# MS5803-02BA.net
KiCad netlist of a schematic drawn in EAGLE
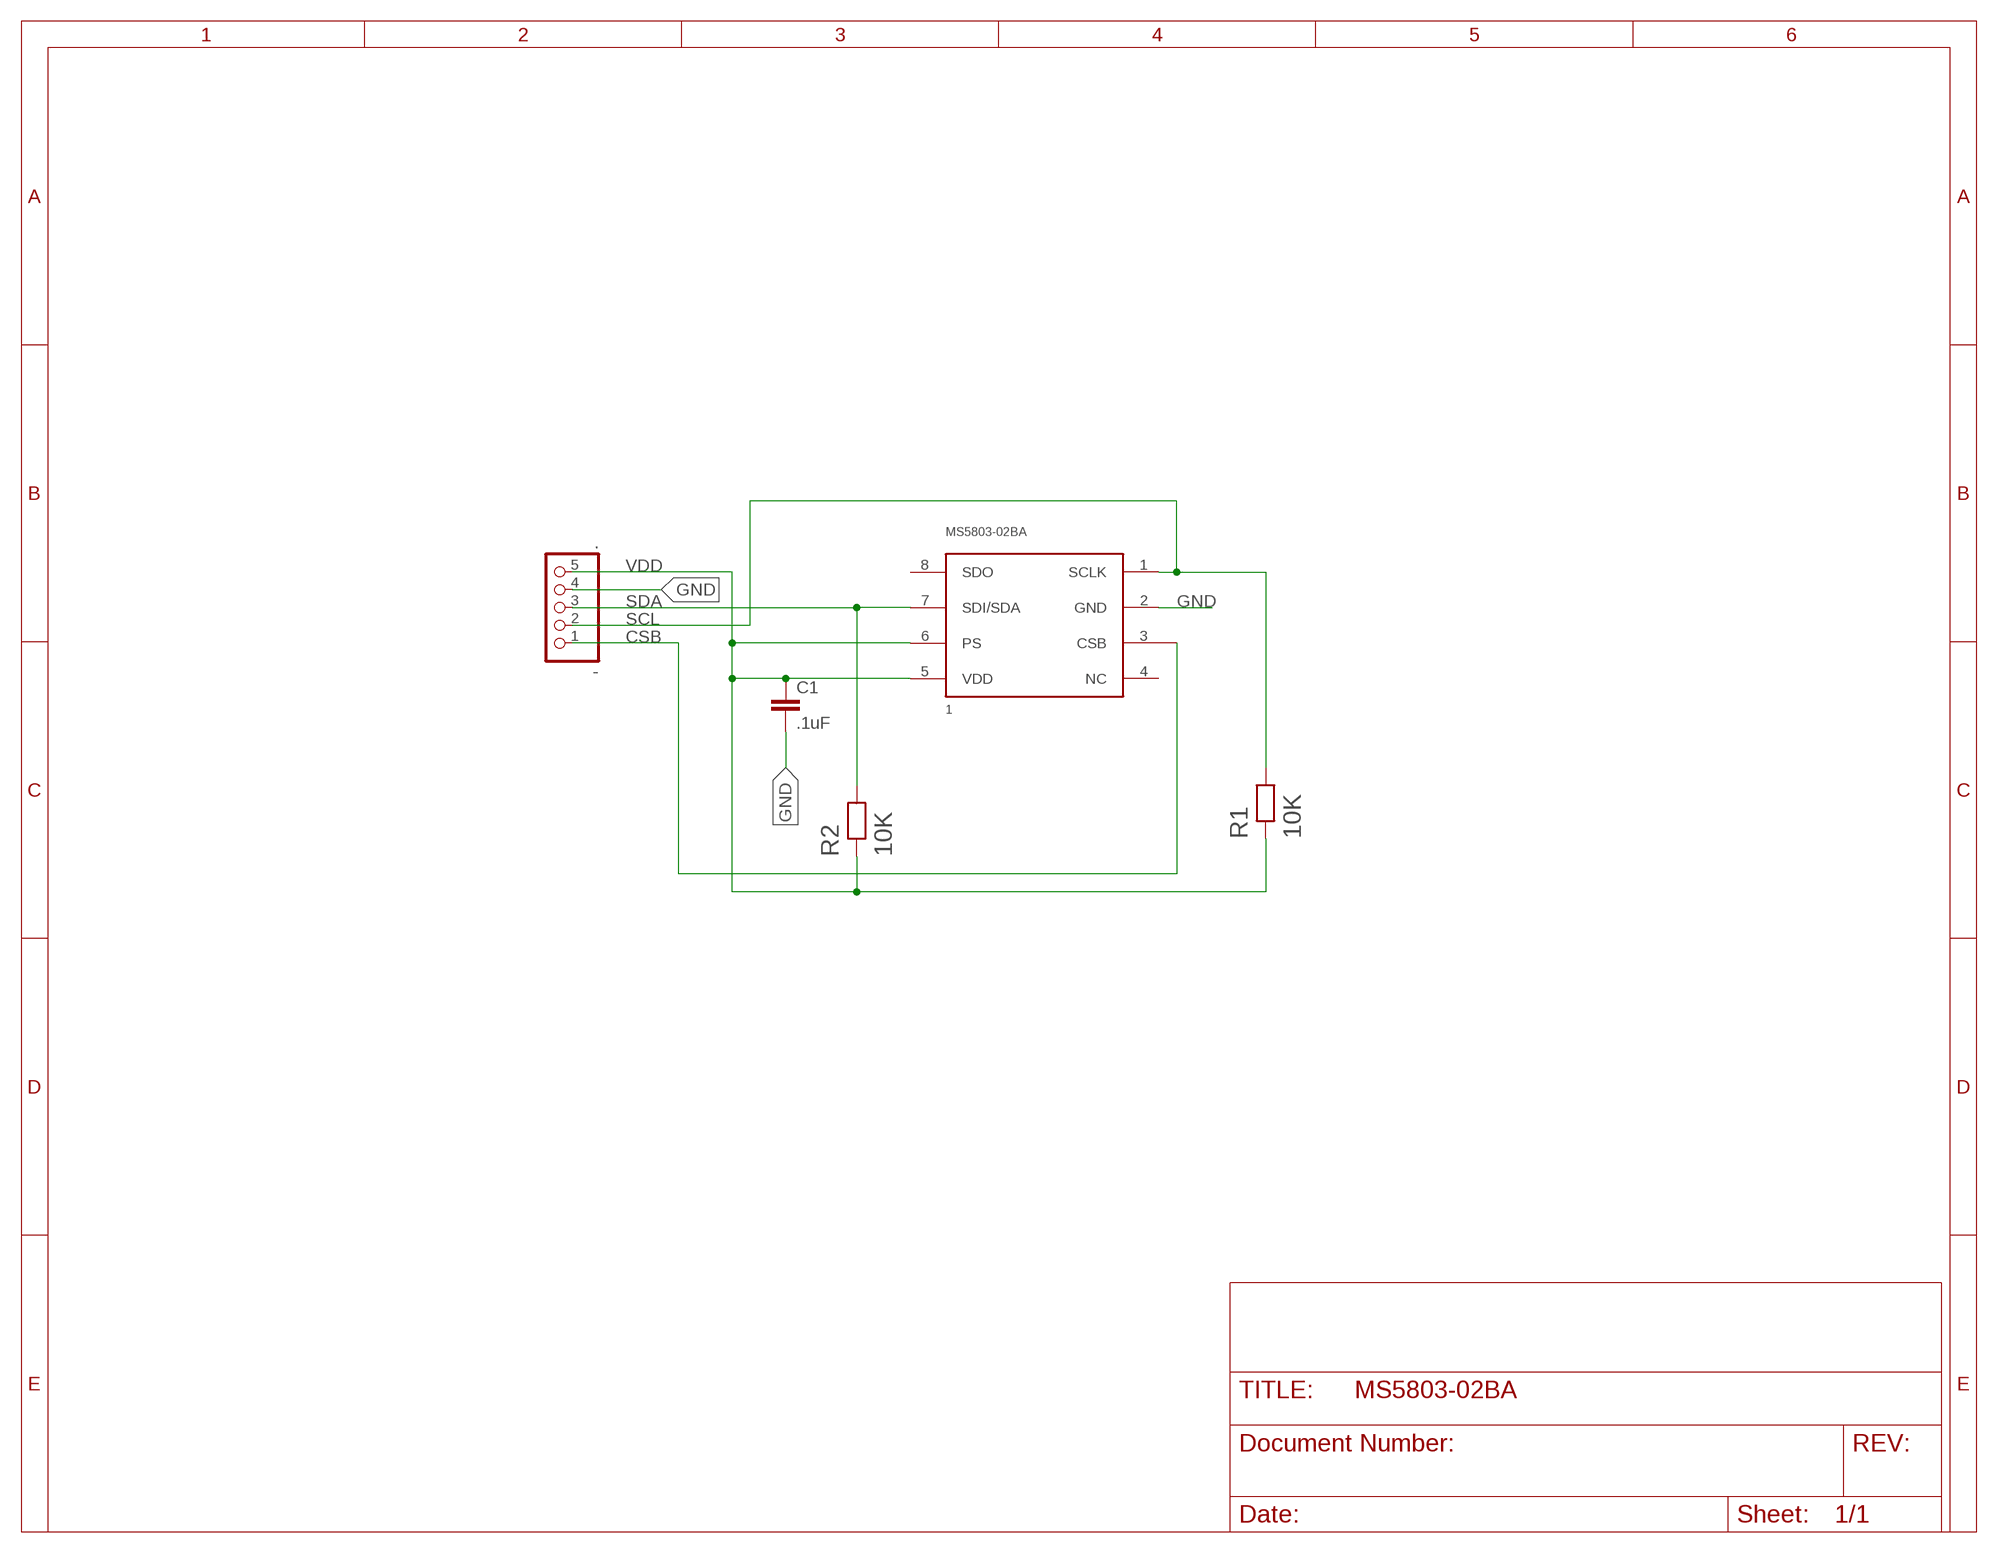
[diagram p0: schematic, sheet 1]

(export (version "E")
  (design (tool "Eeschema 10.0.6"))
  (components
    (comp (ref "-")
      (value ".")
      (footprint "eagle-import:1X05")
      (libsource (lib "eagle-import") (part "PINHD-1X5"))
    )
    (comp (ref "C1")
      (value ".1uF")
      (footprint "eagle-import:C0805")
      (libsource (lib "eagle-import") (part "C-EUC0805"))
    )
    (comp (ref "MS5803-02BA")
      (value "1")
      (footprint "eagle-import:MS5803-02BA")
      (libsource (lib "eagle-import") (part "MS5803-02BASMD"))
    )
    (comp (ref "R1")
      (value "10K")
      (footprint "eagle-import:2012(0805)RESISTOR")
      (libsource (lib "eagle-import") (part "10KOHM_2012(0805)_SMDSMD"))
    )
    (comp (ref "R2")
      (value "10K")
      (footprint "eagle-import:2012(0805)RESISTOR")
      (libsource (lib "eagle-import") (part "10KOHM_2012(0805)_SMDSMD"))
    )
  )
  (nets
    (net (code "1") (name "/CSB") (class "Default")
      (node (ref "-") (pin "1") (pinfunction "1_1") (pintype "passive"))
      (node (ref "MS5803-02BA") (pin "3") (pinfunction "CSB_3") (pintype "bidirectional"))
    )
    (net (code "2") (name "/SCL") (class "Default")
      (node (ref "-") (pin "2") (pinfunction "2_2") (pintype "passive"))
      (node (ref "MS5803-02BA") (pin "1") (pinfunction "SCLK_1") (pintype "bidirectional"))
      (node (ref "R1") (pin "2") (pinfunction "2_2") (pintype "passive"))
    )
    (net (code "3") (name "/SDA") (class "Default")
      (node (ref "-") (pin "3") (pinfunction "3_3") (pintype "passive"))
      (node (ref "MS5803-02BA") (pin "7") (pinfunction "SDI/SDA_7") (pintype "bidirectional"))
      (node (ref "R2") (pin "2") (pinfunction "2_2") (pintype "passive"))
    )
    (net (code "4") (name "/VDD") (class "Default")
      (node (ref "-") (pin "5") (pinfunction "5_5") (pintype "passive"))
      (node (ref "C1") (pin "1") (pinfunction "1_1") (pintype "passive"))
      (node (ref "MS5803-02BA") (pin "5") (pinfunction "VDD_5") (pintype "power_in"))
      (node (ref "MS5803-02BA") (pin "6") (pinfunction "PS_6") (pintype "bidirectional"))
      (node (ref "R1") (pin "1") (pinfunction "1_1") (pintype "passive"))
      (node (ref "R2") (pin "1") (pinfunction "1_1") (pintype "passive"))
    )
    (net (code "5") (name "GND") (class "Default")
      (node (ref "-") (pin "4") (pinfunction "4_4") (pintype "passive"))
      (node (ref "C1") (pin "2") (pinfunction "2_2") (pintype "passive"))
      (node (ref "MS5803-02BA") (pin "2") (pinfunction "GND_2") (pintype "bidirectional"))
    )
    (net (code "6") (name "unconnected-(MS5803-02BA-NC-Pad4)") (class "Default")
      (node (ref "MS5803-02BA") (pin "4") (pinfunction "NC_4") (pintype "no_connect"))
    )
    (net (code "7") (name "unconnected-(MS5803-02BA-SDO-Pad8)") (class "Default")
      (node (ref "MS5803-02BA") (pin "8") (pinfunction "SDO_8") (pintype "bidirectional"))
    )
  )
)
